# charger_1A.net
KiCad netlist of a schematic drawn in Altium Designer
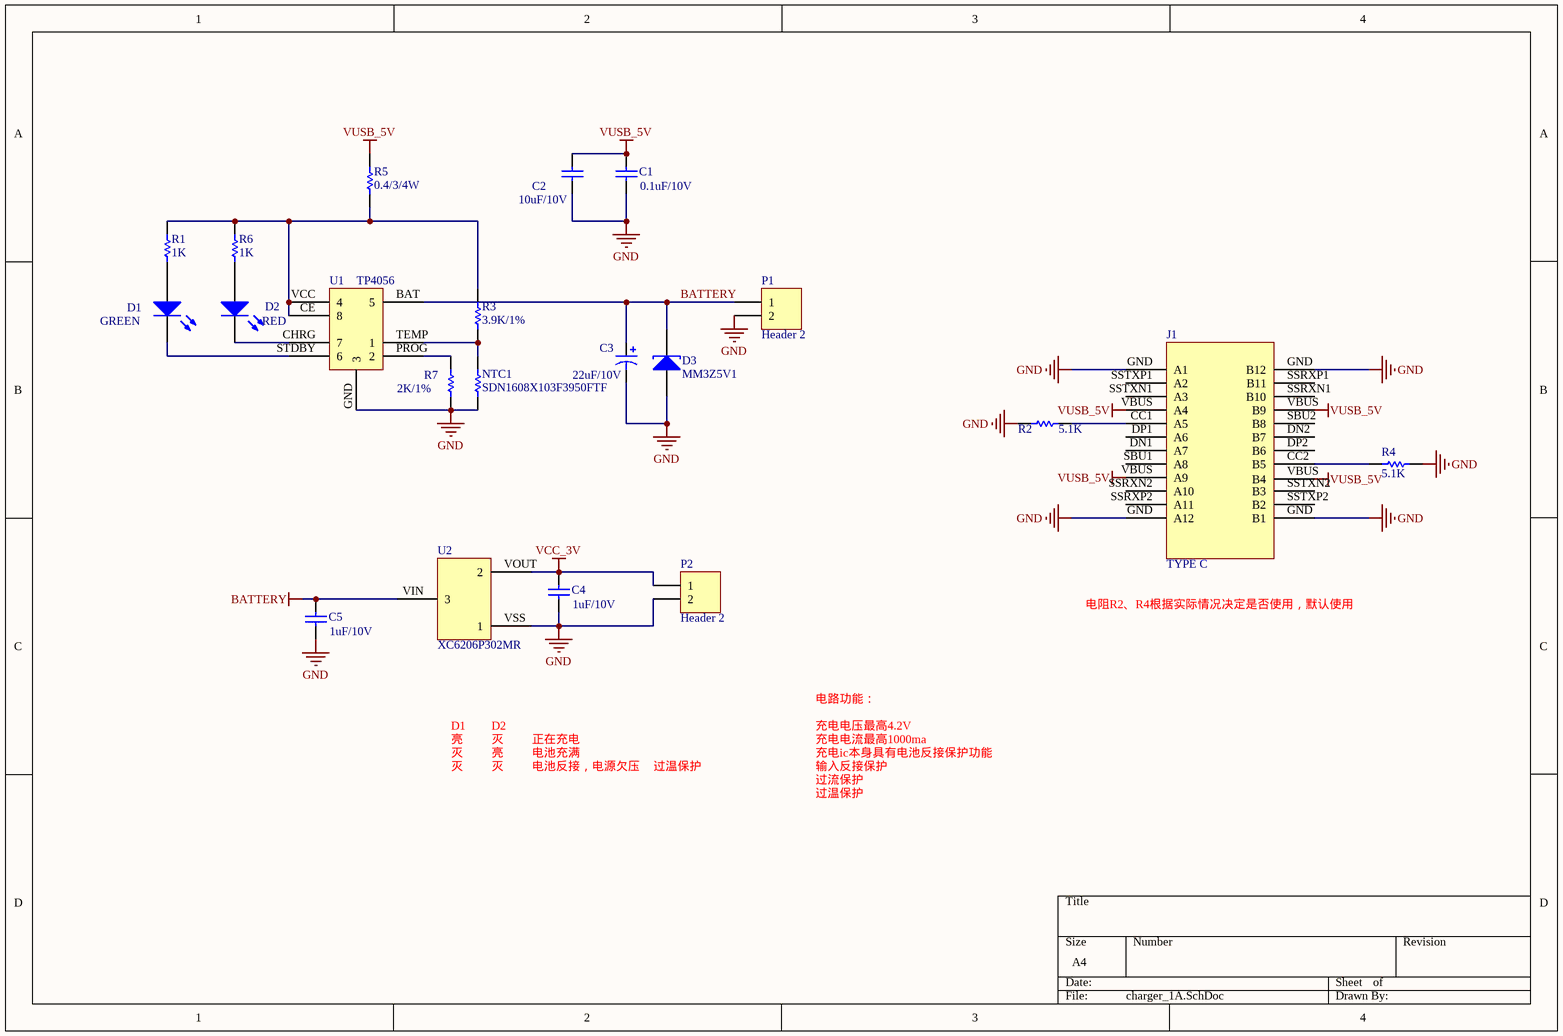
[diagram p0: charger_1A.SchDoc]

(export (version "E")
  (design (tool "Eeschema 10.0.6"))
  (components
    (comp (ref "C1")
      (value "0.1uF/10V")
      (footprint "0603C")
      (description "Capacitor")
      (fields (field (name "PUBLISHER") "Altium Limited"))
      (libsource (lib "Miscellaneous Devices") (part "Cap"))
    )
    (comp (ref "C2")
      (value "10uF/10V")
      (footprint "0603C")
      (description "Capacitor")
      (fields (field (name "PUBLISHER") "Altium Limited"))
      (libsource (lib "Miscellaneous Devices") (part "Cap"))
    )
    (comp (ref "C3")
      (value "22uF/10V")
      (footprint "1210E")
      (description "Polarized Capacitor (Radial)")
      (fields (field (name "PUBLISHER") "Altium Limited"))
      (libsource (lib "Miscellaneous Devices") (part "Cap Pol1"))
    )
    (comp (ref "C4")
      (value "1uF/10V")
      (footprint "0603C")
      (description "Capacitor")
      (fields (field (name "PUBLISHER") "Altium Limited"))
      (libsource (lib "Miscellaneous Devices") (part "Cap"))
    )
    (comp (ref "C5")
      (value "1uF/10V")
      (footprint "0603C")
      (description "Capacitor")
      (fields (field (name "PUBLISHER") "Altium Limited"))
      (libsource (lib "Miscellaneous Devices") (part "Cap"))
    )
    (comp (ref "D1")
      (value "~")
      (footprint "0603LED")
      (description "Typical INFRARED GaAs LED")
      (fields (field (name "PUBLISHER") "GREEN"))
      (libsource (lib "Miscellaneous Devices") (part "LED0"))
    )
    (comp (ref "D2")
      (value "~")
      (footprint "0603LED")
      (description "Typical INFRARED GaAs LED")
      (fields (field (name "PUBLISHER") "RED"))
      (libsource (lib "Miscellaneous Devices") (part "LED0"))
    )
    (comp (ref "D3")
      (value "MM3Z5V1")
      (footprint "SOD323")
      (description "Tunnel Diode - RLC Model")
      (fields (field (name "PUBLISHER") "Altium Limited"))
      (libsource (lib "Miscellaneous Devices") (part "D Tunnel1"))
    )
    (comp (ref "J1") (value "TYPE C") (libsource (lib "CHARGER") (part "TYPE C")))
    (comp (ref "NTC1")
      (value "SDN1608X103F3950FTF")
      (footprint "0603R")
      (description "Semiconductor Resistor")
      (fields (field (name "PUBLISHER") "Altium Limited"))
      (libsource (lib "Miscellaneous Devices") (part "Res Semi"))
    )
    (comp (ref "P1")
      (value "Header 2")
      (footprint "HDR1X2")
      (description "Header, 2-Pin")
      (fields (field (name "PUBLISHER") "Altium Limited"))
      (libsource (lib "Miscellaneous Connectors") (part "Header 2"))
    )
    (comp (ref "P2")
      (value "Header 2")
      (footprint "HDR1X2")
      (description "Header, 2-Pin")
      (fields (field (name "PUBLISHER") "Altium Limited"))
      (libsource (lib "Miscellaneous Connectors") (part "Header 2"))
    )
    (comp (ref "R1")
      (value "1K")
      (footprint "0603R")
      (description "Semiconductor Resistor")
      (fields (field (name "PUBLISHER") "Altium Limited"))
      (libsource (lib "Miscellaneous Devices") (part "Res Semi"))
    )
    (comp (ref "R2")
      (value "5.1K")
      (footprint "0603R")
      (description "Semiconductor Resistor")
      (fields (field (name "PUBLISHER") "Altium Limited"))
      (libsource (lib "Miscellaneous Devices") (part "Res Semi"))
    )
    (comp (ref "R3")
      (value "3.9K/1%")
      (footprint "0603R")
      (description "Semiconductor Resistor")
      (fields (field (name "PUBLISHER") "Altium Limited"))
      (libsource (lib "Miscellaneous Devices") (part "Res Semi"))
    )
    (comp (ref "R4")
      (value "5.1K")
      (footprint "0603R")
      (description "Semiconductor Resistor")
      (fields (field (name "PUBLISHER") "Altium Limited"))
      (libsource (lib "Miscellaneous Devices") (part "Res Semi"))
    )
    (comp (ref "R5")
      (value "0.4/3/4W")
      (footprint "0603R")
      (description "Semiconductor Resistor")
      (fields (field (name "PUBLISHER") "Altium Limited"))
      (libsource (lib "Miscellaneous Devices") (part "Res Semi"))
    )
    (comp (ref "R6")
      (value "1K")
      (footprint "0603R")
      (description "Semiconductor Resistor")
      (fields (field (name "PUBLISHER") "Altium Limited"))
      (libsource (lib "Miscellaneous Devices") (part "Res Semi"))
    )
    (comp (ref "R7")
      (value "2K/1%")
      (footprint "0603R")
      (description "Semiconductor Resistor")
      (fields (field (name "PUBLISHER") "Altium Limited"))
      (libsource (lib "Miscellaneous Devices") (part "Res Semi"))
    )
    (comp (ref "U1") (value "TP4056") (libsource (lib "CHARGER") (part "TP4056")))
    (comp (ref "U2") (value "XC6206P302MR") (libsource (lib "CHARGER") (part "XC6206P302MR")))
  )
  (nets
    (net (code "1") (name "BATTERY") (class "Default")
      (node (ref "C3") (pin "1") (pinfunction "1_1") (pintype "passive"))
      (node (ref "C5") (pin "2") (pinfunction "2_2") (pintype "passive"))
      (node (ref "D3") (pin "2") (pinfunction "K_2") (pintype "passive"))
      (node (ref "P1") (pin "1") (pinfunction "1_1") (pintype "passive"))
      (node (ref "U1") (pin "BAT") (pinfunction "5_BAT") (pintype "passive"))
      (node (ref "U2") (pin "VIN") (pinfunction "3_VIN") (pintype "passive"))
    )
    (net (code "2") (name "GND") (class "Default")
      (node (ref "C1") (pin "1") (pinfunction "1_1") (pintype "passive"))
      (node (ref "C2") (pin "1") (pinfunction "1_1") (pintype "passive"))
      (node (ref "C3") (pin "2") (pinfunction "2_2") (pintype "passive"))
      (node (ref "C4") (pin "1") (pinfunction "1_1") (pintype "passive"))
      (node (ref "C5") (pin "1") (pinfunction "1_1") (pintype "passive"))
      (node (ref "D3") (pin "1") (pinfunction "A_1") (pintype "passive"))
      (node (ref "J1") (pin "GND") (pinfunction "B1_GND") (pintype "passive"))
      (node (ref "NTC1") (pin "2") (pinfunction "2_2") (pintype "passive"))
      (node (ref "P1") (pin "2") (pinfunction "2_2") (pintype "passive"))
      (node (ref "P2") (pin "2") (pinfunction "2_2") (pintype "passive"))
      (node (ref "R2") (pin "2") (pinfunction "2_2") (pintype "passive"))
      (node (ref "R4") (pin "2") (pinfunction "2_2") (pintype "passive"))
      (node (ref "R7") (pin "1") (pinfunction "1_1") (pintype "passive"))
      (node (ref "U1") (pin "GND") (pinfunction "3_GND") (pintype "passive"))
      (node (ref "U2") (pin "VSS") (pinfunction "1_VSS") (pintype "passive"))
    )
    (net (code "3") (name "Net-(D1-A)") (class "Default")
      (node (ref "D1") (pin "1") (pinfunction "A_1") (pintype "passive"))
      (node (ref "R1") (pin "1") (pinfunction "1_1") (pintype "passive"))
    )
    (net (code "4") (name "Net-(D1-K)") (class "Default")
      (node (ref "D1") (pin "2") (pinfunction "K_2") (pintype "passive"))
      (node (ref "U1") (pin "STDBY") (pinfunction "6_STDBY") (pintype "passive"))
    )
    (net (code "5") (name "Net-(D2-A)") (class "Default")
      (node (ref "D2") (pin "1") (pinfunction "A_1") (pintype "passive"))
      (node (ref "R6") (pin "1") (pinfunction "1_1") (pintype "passive"))
    )
    (net (code "6") (name "Net-(D2-K)") (class "Default")
      (node (ref "D2") (pin "2") (pinfunction "K_2") (pintype "passive"))
      (node (ref "U1") (pin "CHRG") (pinfunction "7_CHRG") (pintype "passive"))
    )
    (net (code "7") (name "Net-(J1-A5)") (class "Default")
      (node (ref "J1") (pin "CC1") (pinfunction "A5_CC1") (pintype "passive"))
      (node (ref "R2") (pin "1") (pinfunction "1_1") (pintype "passive"))
    )
    (net (code "8") (name "Net-(J1-B5)") (class "Default")
      (node (ref "J1") (pin "CC2") (pinfunction "B5_CC2") (pintype "passive"))
      (node (ref "R4") (pin "1") (pinfunction "1_1") (pintype "passive"))
    )
    (net (code "9") (name "Net-(U1-1)") (class "Default")
      (node (ref "NTC1") (pin "1") (pinfunction "1_1") (pintype "passive"))
      (node (ref "R3") (pin "2") (pinfunction "2_2") (pintype "passive"))
      (node (ref "U1") (pin "TEMP") (pinfunction "1_TEMP") (pintype "passive"))
    )
    (net (code "10") (name "Net-(U1-2)") (class "Default")
      (node (ref "R7") (pin "2") (pinfunction "2_2") (pintype "passive"))
      (node (ref "U1") (pin "PROG") (pinfunction "2_PROG") (pintype "passive"))
    )
    (net (code "11") (name "Net-(U1-4)") (class "Default")
      (node (ref "R1") (pin "2") (pinfunction "2_2") (pintype "passive"))
      (node (ref "R3") (pin "1") (pinfunction "1_1") (pintype "passive"))
      (node (ref "R5") (pin "2") (pinfunction "2_2") (pintype "passive"))
      (node (ref "R6") (pin "2") (pinfunction "2_2") (pintype "passive"))
      (node (ref "U1") (pin "CE") (pinfunction "8_CE") (pintype "passive"))
      (node (ref "U1") (pin "VCC") (pinfunction "4_VCC") (pintype "passive"))
    )
    (net (code "12") (name "VCC_3V") (class "Default")
      (node (ref "C4") (pin "2") (pinfunction "2_2") (pintype "passive"))
      (node (ref "P2") (pin "1") (pinfunction "1_1") (pintype "passive"))
      (node (ref "U2") (pin "VOUT") (pinfunction "2_VOUT") (pintype "passive"))
    )
    (net (code "13") (name "VUSB_5V") (class "Default")
      (node (ref "C1") (pin "2") (pinfunction "2_2") (pintype "passive"))
      (node (ref "C2") (pin "2") (pinfunction "2_2") (pintype "passive"))
      (node (ref "J1") (pin "VBUS") (pinfunction "A4_VBUS") (pintype "passive"))
      (node (ref "R5") (pin "1") (pinfunction "1_1") (pintype "passive"))
    )
    (net (code "14") (name "unconnected-(J1-A2-PadSSTXP1)") (class "Default")
      (node (ref "J1") (pin "SSTXP1") (pinfunction "A2_SSTXP1") (pintype "passive"))
    )
    (net (code "15") (name "unconnected-(J1-A3-PadSSTXN1)") (class "Default")
      (node (ref "J1") (pin "SSTXN1") (pinfunction "A3_SSTXN1") (pintype "passive"))
    )
    (net (code "16") (name "unconnected-(J1-A6-PadDP1)") (class "Default")
      (node (ref "J1") (pin "DP1") (pinfunction "A6_DP1") (pintype "passive"))
    )
    (net (code "17") (name "unconnected-(J1-A7-PadDN1)") (class "Default")
      (node (ref "J1") (pin "DN1") (pinfunction "A7_DN1") (pintype "passive"))
    )
    (net (code "18") (name "unconnected-(J1-A8-PadSBU1)") (class "Default")
      (node (ref "J1") (pin "SBU1") (pinfunction "A8_SBU1") (pintype "passive"))
    )
    (net (code "19") (name "unconnected-(J1-A10-PadSSRXN2)") (class "Default")
      (node (ref "J1") (pin "SSRXN2") (pinfunction "A10_SSRXN2") (pintype "passive"))
    )
    (net (code "20") (name "unconnected-(J1-A11-PadSSRXP2)") (class "Default")
      (node (ref "J1") (pin "SSRXP2") (pinfunction "A11_SSRXP2") (pintype "passive"))
    )
    (net (code "21") (name "unconnected-(J1-B2-PadSSTXP2)") (class "Default")
      (node (ref "J1") (pin "SSTXP2") (pinfunction "B2_SSTXP2") (pintype "passive"))
    )
    (net (code "22") (name "unconnected-(J1-B3-PadSSTXN2)") (class "Default")
      (node (ref "J1") (pin "SSTXN2") (pinfunction "B3_SSTXN2") (pintype "passive"))
    )
    (net (code "23") (name "unconnected-(J1-B6-PadDP2)") (class "Default")
      (node (ref "J1") (pin "DP2") (pinfunction "B6_DP2") (pintype "passive"))
    )
    (net (code "24") (name "unconnected-(J1-B7-PadDN2)") (class "Default")
      (node (ref "J1") (pin "DN2") (pinfunction "B7_DN2") (pintype "passive"))
    )
    (net (code "25") (name "unconnected-(J1-B8-PadSBU2)") (class "Default")
      (node (ref "J1") (pin "SBU2") (pinfunction "B8_SBU2") (pintype "passive"))
    )
    (net (code "26") (name "unconnected-(J1-B10-PadSSRXN1)") (class "Default")
      (node (ref "J1") (pin "SSRXN1") (pinfunction "B10_SSRXN1") (pintype "passive"))
    )
    (net (code "27") (name "unconnected-(J1-B11-PadSSRXP1)") (class "Default")
      (node (ref "J1") (pin "SSRXP1") (pinfunction "B11_SSRXP1") (pintype "passive"))
    )
  )
)
